# Connectors.net
KiCad netlist of a schematic drawn in Altium Designer
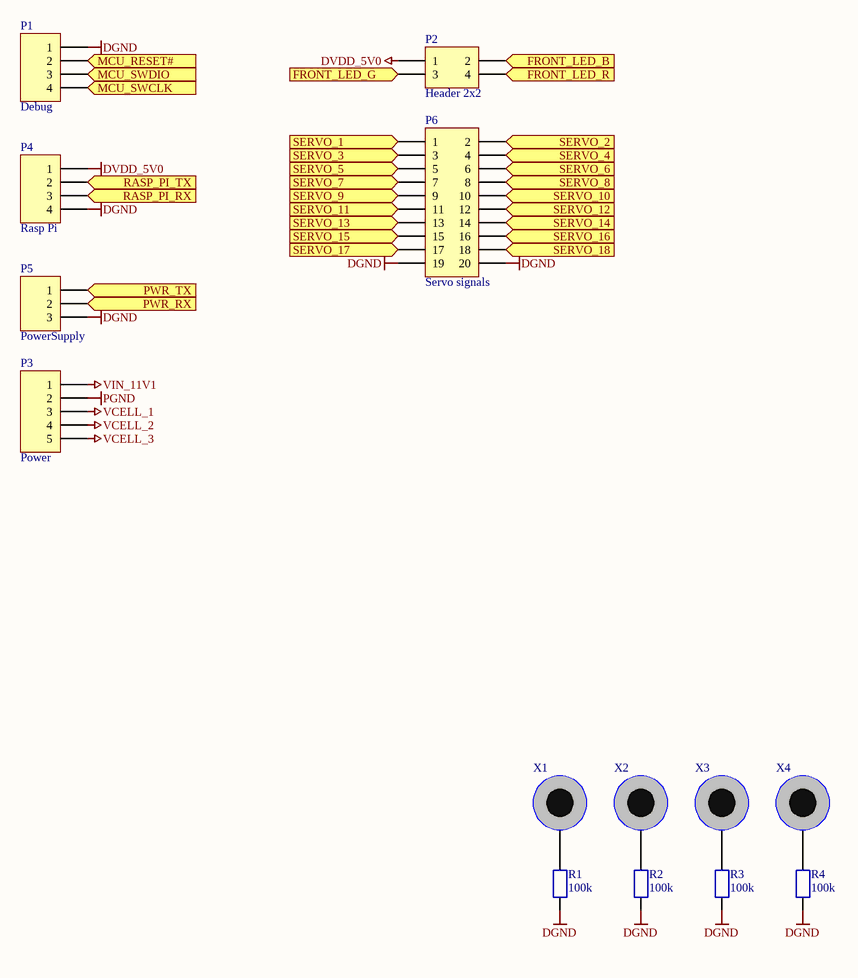
[diagram p0: Connectors.SchDoc]

(export (version "E")
  (design (tool "Eeschema 10.0.6"))
  (components
    (comp (ref "P1")
      (value "Debug")
      (footprint "HDR_SMD_1X4_1.50")
      (description "Header, 4-Pin")
      (fields (field (name "PUBLISHER") "Altium Limited"))
      (libsource (lib "connectors") (part "Header 4"))
    )
    (comp (ref "P2")
      (value "Header 2x2")
      (footprint "HDR_M_2X2_2.54")
      (description "Header, 2-Pin")
      (fields (field (name "PUBLISHER") "Altium Limited"))
      (libsource (lib "connectors") (part "Header 2x2"))
    )
    (comp (ref "P3")
      (value "Power")
      (footprint "HDR_M_1X5_2.54_OUTLINE")
      (description "Header, 5-Pin")
      (fields (field (name "PUBLISHER") "Altium Limited"))
      (libsource (lib "connectors") (part "Header 5"))
    )
    (comp (ref "P4")
      (value "Rasp Pi")
      (footprint "HDR_M_1X4_2.54")
      (description "Header, 4-Pin")
      (fields (field (name "PUBLISHER") "Altium Limited"))
      (libsource (lib "connectors") (part "Header 4"))
    )
    (comp (ref "P5")
      (value "PowerSupply")
      (footprint "HDR_M_1X3_2.54")
      (description "Header, 3-Pin")
      (fields (field (name "PUBLISHER") "Altium Limited"))
      (libsource (lib "connectors") (part "Header 3"))
    )
    (comp (ref "P6")
      (value "Servo signals")
      (footprint "HDR_M_2X10_2.54_OUTLINE")
      (description "Header, 20-Pin")
      (fields (field (name "PUBLISHER") "Altium Limited"))
      (libsource (lib "connectors") (part "Header 2x10"))
    )
    (comp (ref "R1")
      (value "100k")
      (footprint "R_0603/1608")
      (description "Resistor")
      (libsource (lib "passive") (part "Resistor"))
    )
    (comp (ref "R2")
      (value "100k")
      (footprint "R_0603/1608")
      (description "Resistor")
      (libsource (lib "passive") (part "Resistor"))
    )
    (comp (ref "R3")
      (value "100k")
      (footprint "R_0603/1608")
      (description "Resistor")
      (libsource (lib "passive") (part "Resistor"))
    )
    (comp (ref "R4")
      (value "100k")
      (footprint "R_0603/1608")
      (description "Resistor")
      (libsource (lib "passive") (part "Resistor"))
    )
    (comp (ref "X1")
      (value "Mounting hole")
      (footprint "HOLE_M2_D4.0/2.5")
      (description "Hole for screw M3, outline D6")
      (libsource (lib "connectors") (part "Mounting hole"))
    )
    (comp (ref "X2")
      (value "Mounting hole")
      (footprint "HOLE_M2_D4.0/2.5")
      (description "Hole for screw M3, outline D6")
      (libsource (lib "connectors") (part "Mounting hole"))
    )
    (comp (ref "X3")
      (value "Mounting hole")
      (footprint "HOLE_M2_D4.0/2.5")
      (description "Hole for screw M3, outline D6")
      (libsource (lib "connectors") (part "Mounting hole"))
    )
    (comp (ref "X4")
      (value "Mounting hole")
      (footprint "HOLE_M2_D4.0/2.5")
      (description "Hole for screw M3, outline D6")
      (libsource (lib "connectors") (part "Mounting hole"))
    )
  )
  (nets
    (net (code "1") (name "/FRONT_LED_B") (class "Default")
      (node (ref "P2") (pin "2") (pinfunction "2_2") (pintype "passive"))
    )
    (net (code "2") (name "/FRONT_LED_G") (class "Default")
      (node (ref "P2") (pin "3") (pinfunction "3_3") (pintype "passive"))
    )
    (net (code "3") (name "/FRONT_LED_R") (class "Default")
      (node (ref "P2") (pin "4") (pinfunction "4_4") (pintype "passive"))
    )
    (net (code "4") (name "/MCU_RESET#") (class "Default")
      (node (ref "P1") (pin "2") (pinfunction "2_2") (pintype "passive"))
    )
    (net (code "5") (name "/MCU_SWCLK") (class "Default")
      (node (ref "P1") (pin "4") (pinfunction "4_4") (pintype "passive"))
    )
    (net (code "6") (name "/MCU_SWDIO") (class "Default")
      (node (ref "P1") (pin "3") (pinfunction "3_3") (pintype "passive"))
    )
    (net (code "7") (name "/PWR_RX") (class "Default")
      (node (ref "P5") (pin "2") (pinfunction "2_2") (pintype "passive"))
    )
    (net (code "8") (name "/PWR_TX") (class "Default")
      (node (ref "P5") (pin "1") (pinfunction "1_1") (pintype "passive"))
    )
    (net (code "9") (name "/RASP_PI_RX") (class "Default")
      (node (ref "P4") (pin "3") (pinfunction "3_3") (pintype "passive"))
    )
    (net (code "10") (name "/RASP_PI_TX") (class "Default")
      (node (ref "P4") (pin "2") (pinfunction "2_2") (pintype "passive"))
    )
    (net (code "11") (name "/SERVO_1") (class "Default")
      (node (ref "P6") (pin "1") (pinfunction "1_1") (pintype "passive"))
    )
    (net (code "12") (name "/SERVO_2") (class "Default")
      (node (ref "P6") (pin "2") (pinfunction "2_2") (pintype "passive"))
    )
    (net (code "13") (name "/SERVO_3") (class "Default")
      (node (ref "P6") (pin "3") (pinfunction "3_3") (pintype "passive"))
    )
    (net (code "14") (name "/SERVO_4") (class "Default")
      (node (ref "P6") (pin "4") (pinfunction "4_4") (pintype "passive"))
    )
    (net (code "15") (name "/SERVO_5") (class "Default")
      (node (ref "P6") (pin "5") (pinfunction "5_5") (pintype "passive"))
    )
    (net (code "16") (name "/SERVO_6") (class "Default")
      (node (ref "P6") (pin "6") (pinfunction "6_6") (pintype "passive"))
    )
    (net (code "17") (name "/SERVO_7") (class "Default")
      (node (ref "P6") (pin "7") (pinfunction "7_7") (pintype "passive"))
    )
    (net (code "18") (name "/SERVO_8") (class "Default")
      (node (ref "P6") (pin "8") (pinfunction "8_8") (pintype "passive"))
    )
    (net (code "19") (name "/SERVO_9") (class "Default")
      (node (ref "P6") (pin "9") (pinfunction "9_9") (pintype "passive"))
    )
    (net (code "20") (name "/SERVO_10") (class "Default")
      (node (ref "P6") (pin "10") (pinfunction "10_10") (pintype "passive"))
    )
    (net (code "21") (name "/SERVO_11") (class "Default")
      (node (ref "P6") (pin "11") (pinfunction "11_11") (pintype "passive"))
    )
    (net (code "22") (name "/SERVO_12") (class "Default")
      (node (ref "P6") (pin "12") (pinfunction "12_12") (pintype "passive"))
    )
    (net (code "23") (name "/SERVO_13") (class "Default")
      (node (ref "P6") (pin "13") (pinfunction "13_13") (pintype "passive"))
    )
    (net (code "24") (name "/SERVO_14") (class "Default")
      (node (ref "P6") (pin "14") (pinfunction "14_14") (pintype "passive"))
    )
    (net (code "25") (name "/SERVO_15") (class "Default")
      (node (ref "P6") (pin "15") (pinfunction "15_15") (pintype "passive"))
    )
    (net (code "26") (name "/SERVO_16") (class "Default")
      (node (ref "P6") (pin "16") (pinfunction "16_16") (pintype "passive"))
    )
    (net (code "27") (name "/SERVO_17") (class "Default")
      (node (ref "P6") (pin "17") (pinfunction "17_17") (pintype "passive"))
    )
    (net (code "28") (name "/SERVO_18") (class "Default")
      (node (ref "P6") (pin "18") (pinfunction "18_18") (pintype "passive"))
    )
    (net (code "29") (name "DGND") (class "Default")
      (node (ref "P1") (pin "1") (pinfunction "1_1") (pintype "passive"))
      (node (ref "P4") (pin "4") (pinfunction "4_4") (pintype "passive"))
      (node (ref "P5") (pin "3") (pinfunction "3_3") (pintype "passive"))
      (node (ref "P6") (pin "19") (pinfunction "19_19") (pintype "passive"))
      (node (ref "P6") (pin "20") (pinfunction "20_20") (pintype "passive"))
      (node (ref "R1") (pin "2") (pintype "passive"))
      (node (ref "R2") (pin "2") (pintype "passive"))
      (node (ref "R3") (pin "2") (pintype "passive"))
      (node (ref "R4") (pin "2") (pintype "passive"))
    )
    (net (code "30") (name "DVDD_5V0") (class "Default")
      (node (ref "P2") (pin "1") (pinfunction "1_1") (pintype "passive"))
      (node (ref "P4") (pin "1") (pinfunction "1_1") (pintype "passive"))
    )
    (net (code "31") (name "Net-(R1-Pad1)") (class "Default")
      (node (ref "R1") (pin "1") (pintype "passive"))
      (node (ref "X1") (pin "1") (pintype "passive"))
    )
    (net (code "32") (name "Net-(R2-Pad1)") (class "Default")
      (node (ref "R2") (pin "1") (pintype "passive"))
      (node (ref "X2") (pin "1") (pintype "passive"))
    )
    (net (code "33") (name "Net-(R3-Pad1)") (class "Default")
      (node (ref "R3") (pin "1") (pintype "passive"))
      (node (ref "X3") (pin "1") (pintype "passive"))
    )
    (net (code "34") (name "Net-(R4-Pad1)") (class "Default")
      (node (ref "R4") (pin "1") (pintype "passive"))
      (node (ref "X4") (pin "1") (pintype "passive"))
    )
    (net (code "35") (name "PGND") (class "Default")
      (node (ref "P3") (pin "2") (pinfunction "2_2") (pintype "passive"))
    )
    (net (code "36") (name "VCELL_1") (class "Default")
      (node (ref "P3") (pin "3") (pinfunction "3_3") (pintype "passive"))
    )
    (net (code "37") (name "VCELL_2") (class "Default")
      (node (ref "P3") (pin "4") (pinfunction "4_4") (pintype "passive"))
    )
    (net (code "38") (name "VCELL_3") (class "Default")
      (node (ref "P3") (pin "5") (pinfunction "5_5") (pintype "passive"))
    )
    (net (code "39") (name "VIN_11V1") (class "Default")
      (node (ref "P3") (pin "1") (pinfunction "1_1") (pintype "passive"))
    )
  )
)
